# protoshield-wiring.net
KiCad netlist of a schematic drawn in EAGLE
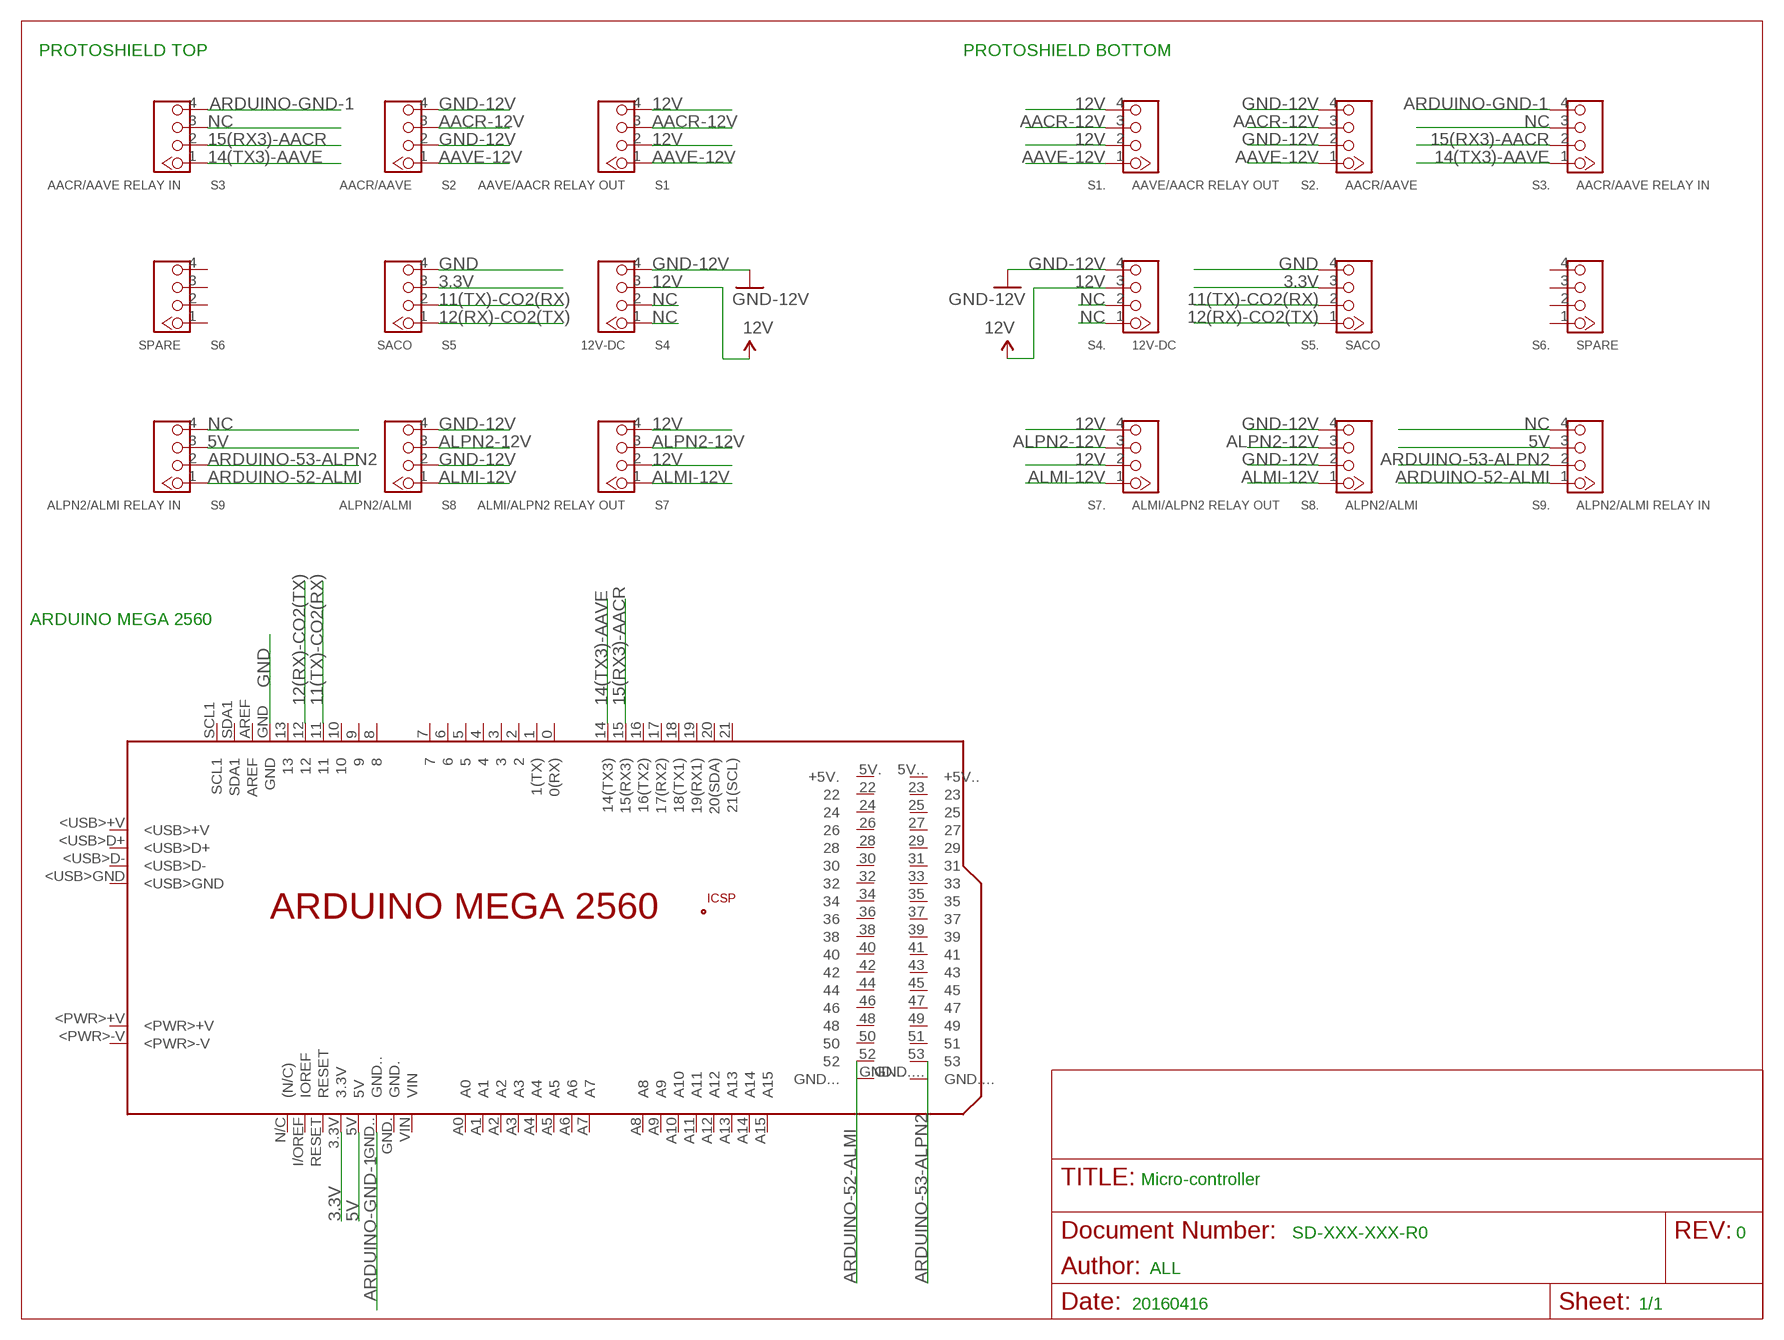
[diagram p0: schematic, sheet 1]

(export (version "E")
  (design (tool "Eeschema 10.0.6"))
  (components
    (comp (ref "PCB1")
      (value "ARDUINO_MEGA2560")
      (footprint "eagle-import:ARDUINO_MEGA2560")
      (libsource (lib "eagle-import") (part "ARDUINO_MEGA2560"))
    )
    (comp (ref "S1")
      (value "AAVE/AACR RELAY OUT")
      (footprint "eagle-import:HW4-2.0")
      (libsource (lib "eagle-import") (part "GROVE-CONNECTOR-DIP(4P-2.0)"))
    )
    (comp (ref "S1.")
      (value "AAVE/AACR RELAY OUT")
      (footprint "eagle-import:HW4-2.0")
      (libsource (lib "eagle-import") (part "GROVE-CONNECTOR-DIP(4P-2.0)"))
    )
    (comp (ref "S2")
      (value "AACR/AAVE")
      (footprint "eagle-import:HW4-2.0")
      (libsource (lib "eagle-import") (part "GROVE-CONNECTOR-DIP(4P-2.0)"))
    )
    (comp (ref "S2.")
      (value "AACR/AAVE")
      (footprint "eagle-import:HW4-2.0")
      (libsource (lib "eagle-import") (part "GROVE-CONNECTOR-DIP(4P-2.0)"))
    )
    (comp (ref "S3")
      (value "AACR/AAVE RELAY IN")
      (footprint "eagle-import:HW4-2.0")
      (libsource (lib "eagle-import") (part "GROVE-CONNECTOR-DIP(4P-2.0)"))
    )
    (comp (ref "S3.")
      (value "AACR/AAVE RELAY IN")
      (footprint "eagle-import:HW4-2.0")
      (libsource (lib "eagle-import") (part "GROVE-CONNECTOR-DIP(4P-2.0)"))
    )
    (comp (ref "S4")
      (value "12V-DC")
      (footprint "eagle-import:HW4-2.0")
      (libsource (lib "eagle-import") (part "GROVE-CONNECTOR-DIP(4P-2.0)"))
    )
    (comp (ref "S4.")
      (value "12V-DC")
      (footprint "eagle-import:HW4-2.0")
      (libsource (lib "eagle-import") (part "GROVE-CONNECTOR-DIP(4P-2.0)"))
    )
    (comp (ref "S5")
      (value "SACO")
      (footprint "eagle-import:HW4-2.0")
      (libsource (lib "eagle-import") (part "GROVE-CONNECTOR-DIP(4P-2.0)"))
    )
    (comp (ref "S5.")
      (value "SACO")
      (footprint "eagle-import:HW4-2.0")
      (libsource (lib "eagle-import") (part "GROVE-CONNECTOR-DIP(4P-2.0)"))
    )
    (comp (ref "S6")
      (value "SPARE")
      (footprint "eagle-import:HW4-2.0")
      (libsource (lib "eagle-import") (part "GROVE-CONNECTOR-DIP(4P-2.0)"))
    )
    (comp (ref "S6.")
      (value "SPARE")
      (footprint "eagle-import:HW4-2.0")
      (libsource (lib "eagle-import") (part "GROVE-CONNECTOR-DIP(4P-2.0)"))
    )
    (comp (ref "S7")
      (value "ALMI/ALPN2 RELAY OUT")
      (footprint "eagle-import:HW4-2.0")
      (libsource (lib "eagle-import") (part "GROVE-CONNECTOR-DIP(4P-2.0)"))
    )
    (comp (ref "S7.")
      (value "ALMI/ALPN2 RELAY OUT")
      (footprint "eagle-import:HW4-2.0")
      (libsource (lib "eagle-import") (part "GROVE-CONNECTOR-DIP(4P-2.0)"))
    )
    (comp (ref "S8")
      (value "ALPN2/ALMI")
      (footprint "eagle-import:HW4-2.0")
      (libsource (lib "eagle-import") (part "GROVE-CONNECTOR-DIP(4P-2.0)"))
    )
    (comp (ref "S8.")
      (value "ALPN2/ALMI")
      (footprint "eagle-import:HW4-2.0")
      (libsource (lib "eagle-import") (part "GROVE-CONNECTOR-DIP(4P-2.0)"))
    )
    (comp (ref "S9")
      (value "ALPN2/ALMI RELAY IN")
      (footprint "eagle-import:HW4-2.0")
      (libsource (lib "eagle-import") (part "GROVE-CONNECTOR-DIP(4P-2.0)"))
    )
    (comp (ref "S9.")
      (value "ALPN2/ALMI RELAY IN")
      (footprint "eagle-import:HW4-2.0")
      (libsource (lib "eagle-import") (part "GROVE-CONNECTOR-DIP(4P-2.0)"))
    )
  )
  (nets
    (net (code "1") (name "/3.3V") (class "Default")
      (node (ref "PCB1") (pin "3.3V") (pinfunction "3.3V_3.3V") (pintype "bidirectional"))
      (node (ref "S5") (pin "3") (pinfunction "3_3") (pintype "bidirectional"))
      (node (ref "S5.") (pin "3") (pinfunction "3_3") (pintype "bidirectional"))
    )
    (net (code "2") (name "/5V") (class "Default")
      (node (ref "PCB1") (pin "5V") (pinfunction "5V_5V") (pintype "bidirectional"))
      (node (ref "S9") (pin "3") (pinfunction "3_3") (pintype "bidirectional"))
      (node (ref "S9.") (pin "3") (pinfunction "3_3") (pintype "bidirectional"))
    )
    (net (code "3") (name "/11(TX)-CO2(RX)") (class "Default")
      (node (ref "PCB1") (pin "11") (pinfunction "11_11") (pintype "bidirectional"))
      (node (ref "S5") (pin "2") (pinfunction "2_2") (pintype "bidirectional"))
      (node (ref "S5.") (pin "2") (pinfunction "2_2") (pintype "bidirectional"))
    )
    (net (code "4") (name "/12(RX)-CO2(TX)") (class "Default")
      (node (ref "PCB1") (pin "12") (pinfunction "12_12") (pintype "bidirectional"))
      (node (ref "S5") (pin "1") (pinfunction "1_1") (pintype "bidirectional"))
      (node (ref "S5.") (pin "1") (pinfunction "1_1") (pintype "bidirectional"))
    )
    (net (code "5") (name "/14(TX3)-AAVE") (class "Default")
      (node (ref "PCB1") (pin "14") (pinfunction "14(TX3)_14") (pintype "bidirectional"))
      (node (ref "S3") (pin "1") (pinfunction "1_1") (pintype "bidirectional"))
      (node (ref "S3.") (pin "1") (pinfunction "1_1") (pintype "bidirectional"))
    )
    (net (code "6") (name "/15(RX3)-AACR") (class "Default")
      (node (ref "PCB1") (pin "15") (pinfunction "15(RX3)_15") (pintype "bidirectional"))
      (node (ref "S3") (pin "2") (pinfunction "2_2") (pintype "bidirectional"))
      (node (ref "S3.") (pin "2") (pinfunction "2_2") (pintype "bidirectional"))
    )
    (net (code "7") (name "/AACR-12V") (class "Default")
      (node (ref "S1") (pin "3") (pinfunction "3_3") (pintype "bidirectional"))
      (node (ref "S1.") (pin "3") (pinfunction "3_3") (pintype "bidirectional"))
      (node (ref "S2") (pin "3") (pinfunction "3_3") (pintype "bidirectional"))
      (node (ref "S2.") (pin "3") (pinfunction "3_3") (pintype "bidirectional"))
    )
    (net (code "8") (name "/AAVE-12V") (class "Default")
      (node (ref "S1") (pin "1") (pinfunction "1_1") (pintype "bidirectional"))
      (node (ref "S1.") (pin "1") (pinfunction "1_1") (pintype "bidirectional"))
      (node (ref "S2") (pin "1") (pinfunction "1_1") (pintype "bidirectional"))
      (node (ref "S2.") (pin "1") (pinfunction "1_1") (pintype "bidirectional"))
    )
    (net (code "9") (name "/ALMI-12V") (class "Default")
      (node (ref "S7") (pin "1") (pinfunction "1_1") (pintype "bidirectional"))
      (node (ref "S7.") (pin "1") (pinfunction "1_1") (pintype "bidirectional"))
      (node (ref "S8") (pin "1") (pinfunction "1_1") (pintype "bidirectional"))
      (node (ref "S8.") (pin "1") (pinfunction "1_1") (pintype "bidirectional"))
    )
    (net (code "10") (name "/ALPN2-12V") (class "Default")
      (node (ref "S7") (pin "3") (pinfunction "3_3") (pintype "bidirectional"))
      (node (ref "S7.") (pin "3") (pinfunction "3_3") (pintype "bidirectional"))
      (node (ref "S8") (pin "3") (pinfunction "3_3") (pintype "bidirectional"))
      (node (ref "S8.") (pin "3") (pinfunction "3_3") (pintype "bidirectional"))
    )
    (net (code "11") (name "/ARDUINO-52-ALMI") (class "Default")
      (node (ref "S9") (pin "1") (pinfunction "1_1") (pintype "bidirectional"))
      (node (ref "S9.") (pin "1") (pinfunction "1_1") (pintype "bidirectional"))
    )
    (net (code "12") (name "/ARDUINO-53-ALPN2") (class "Default")
      (node (ref "S9") (pin "2") (pinfunction "2_2") (pintype "bidirectional"))
      (node (ref "S9.") (pin "2") (pinfunction "2_2") (pintype "bidirectional"))
    )
    (net (code "13") (name "/ARDUINO-GND-1") (class "Default")
      (node (ref "PCB1") (pin "GND..") (pinfunction "GND.._GND..") (pintype "bidirectional"))
      (node (ref "S3") (pin "4") (pinfunction "4_4") (pintype "bidirectional"))
      (node (ref "S3.") (pin "4") (pinfunction "4_4") (pintype "bidirectional"))
    )
    (net (code "14") (name "/GND") (class "Default")
      (node (ref "PCB1") (pin "GND") (pinfunction "GND_GND") (pintype "bidirectional"))
      (node (ref "S5") (pin "4") (pinfunction "4_4") (pintype "bidirectional"))
      (node (ref "S5.") (pin "4") (pinfunction "4_4") (pintype "bidirectional"))
    )
    (net (code "15") (name "/NC") (class "Default")
      (node (ref "S3") (pin "3") (pinfunction "3_3") (pintype "bidirectional"))
      (node (ref "S3.") (pin "3") (pinfunction "3_3") (pintype "bidirectional"))
      (node (ref "S4") (pin "1") (pinfunction "1_1") (pintype "bidirectional"))
      (node (ref "S4") (pin "2") (pinfunction "2_2") (pintype "bidirectional"))
      (node (ref "S4.") (pin "1") (pinfunction "1_1") (pintype "bidirectional"))
      (node (ref "S4.") (pin "2") (pinfunction "2_2") (pintype "bidirectional"))
      (node (ref "S9") (pin "4") (pinfunction "4_4") (pintype "bidirectional"))
      (node (ref "S9.") (pin "4") (pinfunction "4_4") (pintype "bidirectional"))
    )
    (net (code "16") (name "12V") (class "Default")
      (node (ref "S1") (pin "2") (pinfunction "2_2") (pintype "bidirectional"))
      (node (ref "S1") (pin "4") (pinfunction "4_4") (pintype "bidirectional"))
      (node (ref "S1.") (pin "2") (pinfunction "2_2") (pintype "bidirectional"))
      (node (ref "S1.") (pin "4") (pinfunction "4_4") (pintype "bidirectional"))
      (node (ref "S4") (pin "3") (pinfunction "3_3") (pintype "bidirectional"))
      (node (ref "S4.") (pin "3") (pinfunction "3_3") (pintype "bidirectional"))
      (node (ref "S7") (pin "2") (pinfunction "2_2") (pintype "bidirectional"))
      (node (ref "S7") (pin "4") (pinfunction "4_4") (pintype "bidirectional"))
      (node (ref "S7.") (pin "2") (pinfunction "2_2") (pintype "bidirectional"))
      (node (ref "S7.") (pin "4") (pinfunction "4_4") (pintype "bidirectional"))
    )
    (net (code "17") (name "GND-12V") (class "Default")
      (node (ref "S2") (pin "2") (pinfunction "2_2") (pintype "bidirectional"))
      (node (ref "S2") (pin "4") (pinfunction "4_4") (pintype "bidirectional"))
      (node (ref "S2.") (pin "2") (pinfunction "2_2") (pintype "bidirectional"))
      (node (ref "S2.") (pin "4") (pinfunction "4_4") (pintype "bidirectional"))
      (node (ref "S4") (pin "4") (pinfunction "4_4") (pintype "bidirectional"))
      (node (ref "S4.") (pin "4") (pinfunction "4_4") (pintype "bidirectional"))
      (node (ref "S8") (pin "2") (pinfunction "2_2") (pintype "bidirectional"))
      (node (ref "S8") (pin "4") (pinfunction "4_4") (pintype "bidirectional"))
      (node (ref "S8.") (pin "2") (pinfunction "2_2") (pintype "bidirectional"))
      (node (ref "S8.") (pin "4") (pinfunction "4_4") (pintype "bidirectional"))
    )
    (net (code "18") (name "unconnected-(PCB1-(N{slash}C)-PadN{slash}C)") (class "Default")
      (node (ref "PCB1") (pin "N/C") (pinfunction "(N/C)_N/C") (pintype "bidirectional"))
    )
    (net (code "19") (name "unconnected-(PCB1-+5V.-Pad5V.)") (class "Default")
      (node (ref "PCB1") (pin "5V.") (pinfunction "+5V._5V.") (pintype "bidirectional"))
    )
    (net (code "20") (name "unconnected-(PCB1-+5V..-Pad5V..)") (class "Default")
      (node (ref "PCB1") (pin "5V..") (pinfunction "+5V.._5V..") (pintype "bidirectional"))
    )
    (net (code "21") (name "unconnected-(PCB1-0(RX)-Pad0)") (class "Default")
      (node (ref "PCB1") (pin "0") (pinfunction "0(RX)_0") (pintype "bidirectional"))
    )
    (net (code "22") (name "unconnected-(PCB1-1(TX)-Pad1)") (class "Default")
      (node (ref "PCB1") (pin "1") (pinfunction "1(TX)_1") (pintype "bidirectional"))
    )
    (net (code "23") (name "unconnected-(PCB1-16(TX2)-Pad16)") (class "Default")
      (node (ref "PCB1") (pin "16") (pinfunction "16(TX2)_16") (pintype "bidirectional"))
    )
    (net (code "24") (name "unconnected-(PCB1-17(RX2)-Pad17)") (class "Default")
      (node (ref "PCB1") (pin "17") (pinfunction "17(RX2)_17") (pintype "bidirectional"))
    )
    (net (code "25") (name "unconnected-(PCB1-18(TX1)-Pad18)") (class "Default")
      (node (ref "PCB1") (pin "18") (pinfunction "18(TX1)_18") (pintype "bidirectional"))
    )
    (net (code "26") (name "unconnected-(PCB1-19(RX1)-Pad19)") (class "Default")
      (node (ref "PCB1") (pin "19") (pinfunction "19(RX1)_19") (pintype "bidirectional"))
    )
    (net (code "27") (name "unconnected-(PCB1-20(SDA)-Pad20)") (class "Default")
      (node (ref "PCB1") (pin "20") (pinfunction "20(SDA)_20") (pintype "bidirectional"))
    )
    (net (code "28") (name "unconnected-(PCB1-21(SCL)-Pad21)") (class "Default")
      (node (ref "PCB1") (pin "21") (pinfunction "21(SCL)_21") (pintype "bidirectional"))
    )
    (net (code "29") (name "unconnected-(PCB1-IOREF-PadI{slash}OREF)") (class "Default")
      (node (ref "PCB1") (pin "I/OREF") (pinfunction "IOREF_I/OREF") (pintype "bidirectional"))
    )
    (net (code "30") (name "unconnected-(PCB1-Pad+5V_)") (class "Default")
      (node (ref "PCB1") (pin "+5V_") (pinfunction "+5V__+5V_") (pintype "bidirectional"))
    )
    (net (code "31") (name "unconnected-(PCB1-Pad2)") (class "Default")
      (node (ref "PCB1") (pin "2") (pinfunction "2_2") (pintype "bidirectional"))
    )
    (net (code "32") (name "unconnected-(PCB1-Pad3)") (class "Default")
      (node (ref "PCB1") (pin "3") (pinfunction "3_3") (pintype "bidirectional"))
    )
    (net (code "33") (name "unconnected-(PCB1-Pad4)") (class "Default")
      (node (ref "PCB1") (pin "4") (pinfunction "4_4") (pintype "bidirectional"))
    )
    (net (code "34") (name "unconnected-(PCB1-Pad5)") (class "Default")
      (node (ref "PCB1") (pin "5") (pinfunction "5_5") (pintype "bidirectional"))
    )
    (net (code "35") (name "unconnected-(PCB1-Pad6)") (class "Default")
      (node (ref "PCB1") (pin "6") (pinfunction "6_6") (pintype "bidirectional"))
    )
    (net (code "36") (name "unconnected-(PCB1-Pad7)") (class "Default")
      (node (ref "PCB1") (pin "7") (pinfunction "7_7") (pintype "bidirectional"))
    )
    (net (code "37") (name "unconnected-(PCB1-Pad8)") (class "Default")
      (node (ref "PCB1") (pin "8") (pinfunction "8_8") (pintype "bidirectional"))
    )
    (net (code "38") (name "unconnected-(PCB1-Pad9)") (class "Default")
      (node (ref "PCB1") (pin "9") (pinfunction "9_9") (pintype "bidirectional"))
    )
    (net (code "39") (name "unconnected-(PCB1-Pad10)") (class "Default")
      (node (ref "PCB1") (pin "10") (pinfunction "10_10") (pintype "bidirectional"))
    )
    (net (code "40") (name "unconnected-(PCB1-Pad13)") (class "Default")
      (node (ref "PCB1") (pin "13") (pinfunction "13_13") (pintype "bidirectional"))
    )
    (net (code "41") (name "unconnected-(PCB1-Pad22)") (class "Default")
      (node (ref "PCB1") (pin "22") (pinfunction "22_22") (pintype "bidirectional"))
    )
    (net (code "42") (name "unconnected-(PCB1-Pad23)") (class "Default")
      (node (ref "PCB1") (pin "23") (pinfunction "23_23") (pintype "bidirectional"))
    )
    (net (code "43") (name "unconnected-(PCB1-Pad24)") (class "Default")
      (node (ref "PCB1") (pin "24") (pinfunction "24_24") (pintype "bidirectional"))
    )
    (net (code "44") (name "unconnected-(PCB1-Pad25)") (class "Default")
      (node (ref "PCB1") (pin "25") (pinfunction "25_25") (pintype "bidirectional"))
    )
    (net (code "45") (name "unconnected-(PCB1-Pad26)") (class "Default")
      (node (ref "PCB1") (pin "26") (pinfunction "26_26") (pintype "bidirectional"))
    )
    (net (code "46") (name "unconnected-(PCB1-Pad27)") (class "Default")
      (node (ref "PCB1") (pin "27") (pinfunction "27_27") (pintype "bidirectional"))
    )
    (net (code "47") (name "unconnected-(PCB1-Pad28)") (class "Default")
      (node (ref "PCB1") (pin "28") (pinfunction "28_28") (pintype "bidirectional"))
    )
    (net (code "48") (name "unconnected-(PCB1-Pad29)") (class "Default")
      (node (ref "PCB1") (pin "29") (pinfunction "29_29") (pintype "bidirectional"))
    )
    (net (code "49") (name "unconnected-(PCB1-Pad30)") (class "Default")
      (node (ref "PCB1") (pin "30") (pinfunction "30_30") (pintype "bidirectional"))
    )
    (net (code "50") (name "unconnected-(PCB1-Pad31)") (class "Default")
      (node (ref "PCB1") (pin "31") (pinfunction "31_31") (pintype "bidirectional"))
    )
    (net (code "51") (name "unconnected-(PCB1-Pad32)") (class "Default")
      (node (ref "PCB1") (pin "32") (pinfunction "32_32") (pintype "bidirectional"))
    )
    (net (code "52") (name "unconnected-(PCB1-Pad33)") (class "Default")
      (node (ref "PCB1") (pin "33") (pinfunction "33_33") (pintype "bidirectional"))
    )
    (net (code "53") (name "unconnected-(PCB1-Pad34)") (class "Default")
      (node (ref "PCB1") (pin "34") (pinfunction "34_34") (pintype "bidirectional"))
    )
    (net (code "54") (name "unconnected-(PCB1-Pad35)") (class "Default")
      (node (ref "PCB1") (pin "35") (pinfunction "35_35") (pintype "bidirectional"))
    )
    (net (code "55") (name "unconnected-(PCB1-Pad36)") (class "Default")
      (node (ref "PCB1") (pin "36") (pinfunction "36_36") (pintype "bidirectional"))
    )
    (net (code "56") (name "unconnected-(PCB1-Pad37)") (class "Default")
      (node (ref "PCB1") (pin "37") (pinfunction "37_37") (pintype "bidirectional"))
    )
    (net (code "57") (name "unconnected-(PCB1-Pad38)") (class "Default")
      (node (ref "PCB1") (pin "38") (pinfunction "38_38") (pintype "bidirectional"))
    )
    (net (code "58") (name "unconnected-(PCB1-Pad39)") (class "Default")
      (node (ref "PCB1") (pin "39") (pinfunction "39_39") (pintype "bidirectional"))
    )
    (net (code "59") (name "unconnected-(PCB1-Pad40)") (class "Default")
      (node (ref "PCB1") (pin "40") (pinfunction "40_40") (pintype "bidirectional"))
    )
    (net (code "60") (name "unconnected-(PCB1-Pad41)") (class "Default")
      (node (ref "PCB1") (pin "41") (pinfunction "41_41") (pintype "bidirectional"))
    )
    (net (code "61") (name "unconnected-(PCB1-Pad42)") (class "Default")
      (node (ref "PCB1") (pin "42") (pinfunction "42_42") (pintype "bidirectional"))
    )
    (net (code "62") (name "unconnected-(PCB1-Pad43)") (class "Default")
      (node (ref "PCB1") (pin "43") (pinfunction "43_43") (pintype "bidirectional"))
    )
    (net (code "63") (name "unconnected-(PCB1-Pad44)") (class "Default")
      (node (ref "PCB1") (pin "44") (pinfunction "44_44") (pintype "bidirectional"))
    )
    (net (code "64") (name "unconnected-(PCB1-Pad45)") (class "Default")
      (node (ref "PCB1") (pin "45") (pinfunction "45_45") (pintype "bidirectional"))
    )
    (net (code "65") (name "unconnected-(PCB1-Pad46)") (class "Default")
      (node (ref "PCB1") (pin "46") (pinfunction "46_46") (pintype "bidirectional"))
    )
    (net (code "66") (name "unconnected-(PCB1-Pad47)") (class "Default")
      (node (ref "PCB1") (pin "47") (pinfunction "47_47") (pintype "bidirectional"))
    )
    (net (code "67") (name "unconnected-(PCB1-Pad48)") (class "Default")
      (node (ref "PCB1") (pin "48") (pinfunction "48_48") (pintype "bidirectional"))
    )
    (net (code "68") (name "unconnected-(PCB1-Pad49)") (class "Default")
      (node (ref "PCB1") (pin "49") (pinfunction "49_49") (pintype "bidirectional"))
    )
    (net (code "69") (name "unconnected-(PCB1-Pad50)") (class "Default")
      (node (ref "PCB1") (pin "50") (pinfunction "50_50") (pintype "bidirectional"))
    )
    (net (code "70") (name "unconnected-(PCB1-Pad51)") (class "Default")
      (node (ref "PCB1") (pin "51") (pinfunction "51_51") (pintype "bidirectional"))
    )
    (net (code "71") (name "unconnected-(PCB1-Pad52)") (class "Default")
      (node (ref "PCB1") (pin "52") (pinfunction "52_52") (pintype "bidirectional"))
    )
    (net (code "72") (name "unconnected-(PCB1-Pad53)") (class "Default")
      (node (ref "PCB1") (pin "53") (pinfunction "53_53") (pintype "bidirectional"))
    )
    (net (code "73") (name "unconnected-(PCB1-Pad<PWR>+V)") (class "Default")
      (node (ref "PCB1") (pin "<PWR>+V") (pinfunction "<PWR>+V_<PWR>+V") (pintype "no_connect"))
    )
    (net (code "74") (name "unconnected-(PCB1-Pad<PWR>-V)") (class "Default")
      (node (ref "PCB1") (pin "<PWR>-V") (pinfunction "<PWR>-V_<PWR>-V") (pintype "no_connect"))
    )
    (net (code "75") (name "unconnected-(PCB1-Pad<USB>+V)") (class "Default")
      (node (ref "PCB1") (pin "<USB>+V") (pinfunction "<USB>+V_<USB>+V") (pintype "no_connect"))
    )
    (net (code "76") (name "unconnected-(PCB1-Pad<USB>D+)") (class "Default")
      (node (ref "PCB1") (pin "<USB>D+") (pinfunction "<USB>D+_<USB>D+") (pintype "no_connect"))
    )
    (net (code "77") (name "unconnected-(PCB1-Pad<USB>D-)") (class "Default")
      (node (ref "PCB1") (pin "<USB>D-") (pinfunction "<USB>D-_<USB>D-") (pintype "no_connect"))
    )
    (net (code "78") (name "unconnected-(PCB1-Pad<USB>GND)") (class "Default")
      (node (ref "PCB1") (pin "<USB>GND") (pinfunction "<USB>GND_<USB>GND") (pintype "no_connect"))
    )
    (net (code "79") (name "unconnected-(PCB1-PadA0)") (class "Default")
      (node (ref "PCB1") (pin "A0") (pinfunction "A0_A0") (pintype "bidirectional"))
    )
    (net (code "80") (name "unconnected-(PCB1-PadA1)") (class "Default")
      (node (ref "PCB1") (pin "A1") (pinfunction "A1_A1") (pintype "bidirectional"))
    )
    (net (code "81") (name "unconnected-(PCB1-PadA2)") (class "Default")
      (node (ref "PCB1") (pin "A2") (pinfunction "A2_A2") (pintype "bidirectional"))
    )
    (net (code "82") (name "unconnected-(PCB1-PadA3)") (class "Default")
      (node (ref "PCB1") (pin "A3") (pinfunction "A3_A3") (pintype "bidirectional"))
    )
    (net (code "83") (name "unconnected-(PCB1-PadA4)") (class "Default")
      (node (ref "PCB1") (pin "A4") (pinfunction "A4_A4") (pintype "bidirectional"))
    )
    (net (code "84") (name "unconnected-(PCB1-PadA5)") (class "Default")
      (node (ref "PCB1") (pin "A5") (pinfunction "A5_A5") (pintype "bidirectional"))
    )
    (net (code "85") (name "unconnected-(PCB1-PadA6)") (class "Default")
      (node (ref "PCB1") (pin "A6") (pinfunction "A6_A6") (pintype "bidirectional"))
    )
    (net (code "86") (name "unconnected-(PCB1-PadA7)") (class "Default")
      (node (ref "PCB1") (pin "A7") (pinfunction "A7_A7") (pintype "bidirectional"))
    )
    (net (code "87") (name "unconnected-(PCB1-PadA8)") (class "Default")
      (node (ref "PCB1") (pin "A8") (pinfunction "A8_A8") (pintype "bidirectional"))
    )
    (net (code "88") (name "unconnected-(PCB1-PadA9)") (class "Default")
      (node (ref "PCB1") (pin "A9") (pinfunction "A9_A9") (pintype "bidirectional"))
    )
    (net (code "89") (name "unconnected-(PCB1-PadA10)") (class "Default")
      (node (ref "PCB1") (pin "A10") (pinfunction "A10_A10") (pintype "bidirectional"))
    )
    (net (code "90") (name "unconnected-(PCB1-PadA11)") (class "Default")
      (node (ref "PCB1") (pin "A11") (pinfunction "A11_A11") (pintype "bidirectional"))
    )
    (net (code "91") (name "unconnected-(PCB1-PadA12)") (class "Default")
      (node (ref "PCB1") (pin "A12") (pinfunction "A12_A12") (pintype "bidirectional"))
    )
    (net (code "92") (name "unconnected-(PCB1-PadA13)") (class "Default")
      (node (ref "PCB1") (pin "A13") (pinfunction "A13_A13") (pintype "bidirectional"))
    )
    (net (code "93") (name "unconnected-(PCB1-PadA14)") (class "Default")
      (node (ref "PCB1") (pin "A14") (pinfunction "A14_A14") (pintype "bidirectional"))
    )
    (net (code "94") (name "unconnected-(PCB1-PadA15)") (class "Default")
      (node (ref "PCB1") (pin "A15") (pinfunction "A15_A15") (pintype "bidirectional"))
    )
    (net (code "95") (name "unconnected-(PCB1-PadAREF)") (class "Default")
      (node (ref "PCB1") (pin "AREF") (pinfunction "AREF_AREF") (pintype "bidirectional"))
    )
    (net (code "96") (name "unconnected-(PCB1-PadGND.)") (class "Default")
      (node (ref "PCB1") (pin "GND.") (pinfunction "GND._GND.") (pintype "bidirectional"))
    )
    (net (code "97") (name "unconnected-(PCB1-PadGND...)") (class "Default")
      (node (ref "PCB1") (pin "GND...") (pinfunction "GND..._GND...") (pintype "bidirectional"))
    )
    (net (code "98") (name "unconnected-(PCB1-PadGND....)") (class "Default")
      (node (ref "PCB1") (pin "GND....") (pinfunction "GND...._GND....") (pintype "bidirectional"))
    )
    (net (code "99") (name "unconnected-(PCB1-PadGND__)") (class "Default")
      (node (ref "PCB1") (pin "GND__") (pinfunction "GND___GND__") (pintype "bidirectional"))
    )
    (net (code "100") (name "unconnected-(PCB1-PadMISO)") (class "Default")
      (node (ref "PCB1") (pin "MISO") (pinfunction "MISO_MISO") (pintype "bidirectional"))
    )
    (net (code "101") (name "unconnected-(PCB1-PadMOSI)") (class "Default")
      (node (ref "PCB1") (pin "MOSI") (pinfunction "MOSI_MOSI") (pintype "bidirectional"))
    )
    (net (code "102") (name "unconnected-(PCB1-PadRESET)") (class "Default")
      (node (ref "PCB1") (pin "RESET") (pinfunction "RESET_RESET") (pintype "bidirectional"))
    )
    (net (code "103") (name "unconnected-(PCB1-PadRESET.)") (class "Default")
      (node (ref "PCB1") (pin "RESET.") (pinfunction "RESET._RESET.") (pintype "bidirectional"))
    )
    (net (code "104") (name "unconnected-(PCB1-PadSCK)") (class "Default")
      (node (ref "PCB1") (pin "SCK") (pinfunction "SCK_SCK") (pintype "bidirectional"))
    )
    (net (code "105") (name "unconnected-(PCB1-PadSCL1)") (class "Default")
      (node (ref "PCB1") (pin "SCL1") (pinfunction "SCL1_SCL1") (pintype "bidirectional"))
    )
    (net (code "106") (name "unconnected-(PCB1-PadSDA1)") (class "Default")
      (node (ref "PCB1") (pin "SDA1") (pinfunction "SDA1_SDA1") (pintype "bidirectional"))
    )
    (net (code "107") (name "unconnected-(PCB1-PadVIN)") (class "Default")
      (node (ref "PCB1") (pin "VIN") (pinfunction "VIN_VIN") (pintype "bidirectional"))
    )
    (net (code "108") (name "unconnected-(S6-Pad1)") (class "Default")
      (node (ref "S6") (pin "1") (pinfunction "1_1") (pintype "bidirectional"))
    )
    (net (code "109") (name "unconnected-(S6-Pad2)") (class "Default")
      (node (ref "S6") (pin "2") (pinfunction "2_2") (pintype "bidirectional"))
    )
    (net (code "110") (name "unconnected-(S6-Pad3)") (class "Default")
      (node (ref "S6") (pin "3") (pinfunction "3_3") (pintype "bidirectional"))
    )
    (net (code "111") (name "unconnected-(S6-Pad4)") (class "Default")
      (node (ref "S6") (pin "4") (pinfunction "4_4") (pintype "bidirectional"))
    )
    (net (code "112") (name "unconnected-(S6.-Pad1)") (class "Default")
      (node (ref "S6.") (pin "1") (pinfunction "1_1") (pintype "bidirectional"))
    )
    (net (code "113") (name "unconnected-(S6.-Pad2)") (class "Default")
      (node (ref "S6.") (pin "2") (pinfunction "2_2") (pintype "bidirectional"))
    )
    (net (code "114") (name "unconnected-(S6.-Pad3)") (class "Default")
      (node (ref "S6.") (pin "3") (pinfunction "3_3") (pintype "bidirectional"))
    )
    (net (code "115") (name "unconnected-(S6.-Pad4)") (class "Default")
      (node (ref "S6.") (pin "4") (pinfunction "4_4") (pintype "bidirectional"))
    )
  )
)
